# BOTTOM_1P.net
KiCad netlist of a schematic drawn in EAGLE
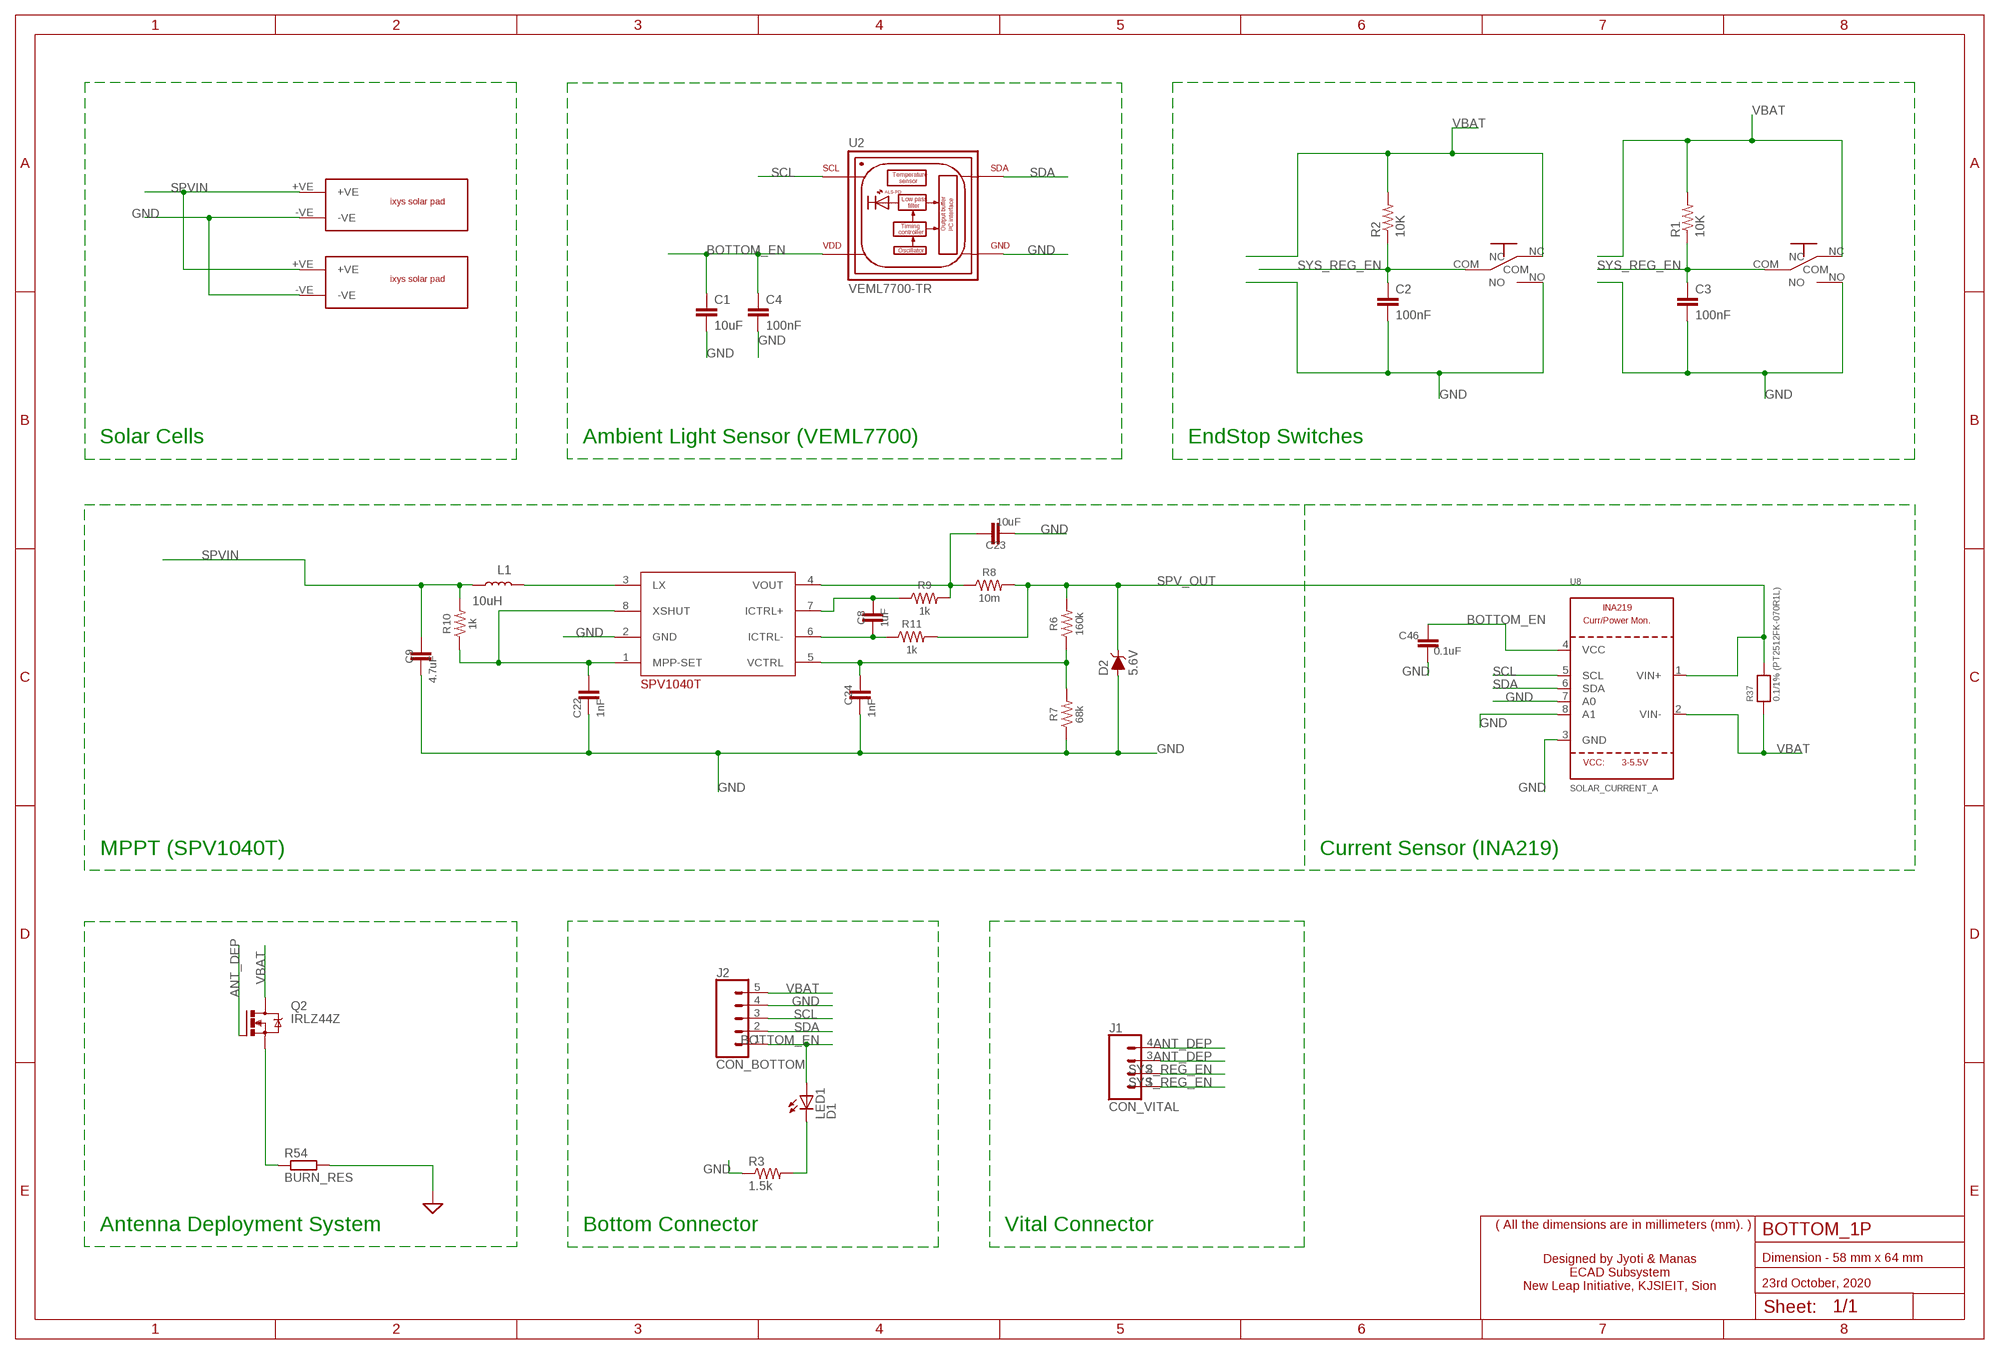
[diagram p0: schematic, sheet 1]

(export (version "E")
  (design (tool "Eeschema 10.0.6"))
  (components
    (comp (ref "C1")
      (value "10uF")
      (footprint "eagle-import:0603")
      (libsource (lib "eagle-import") (part "2.2NF/2200PF-0603-50V-10%"))
    )
    (comp (ref "C2")
      (value "100nF")
      (footprint "eagle-import:0805")
      (libsource (lib "eagle-import") (part "CAP0805"))
    )
    (comp (ref "C3")
      (value "100nF")
      (footprint "eagle-import:0805")
      (libsource (lib "eagle-import") (part "CAP0805"))
    )
    (comp (ref "C4")
      (value "100nF")
      (footprint "eagle-import:0603")
      (libsource (lib "eagle-import") (part "2.2NF/2200PF-0603-50V-10%"))
    )
    (comp (ref "C8")
      (value "1uF")
      (footprint "eagle-import:0603")
      (libsource (lib "eagle-import") (part "10UF-0603-6.3V-20%"))
    )
    (comp (ref "C9")
      (value "4.7uF")
      (footprint "eagle-import:0603")
      (libsource (lib "eagle-import") (part "10UF-0603-6.3V-20%"))
    )
    (comp (ref "C22")
      (value "1nF")
      (footprint "eagle-import:0603")
      (libsource (lib "eagle-import") (part "10UF-0603-6.3V-20%"))
    )
    (comp (ref "C23")
      (value "10uF")
      (footprint "eagle-import:0603")
      (libsource (lib "eagle-import") (part "10UF-0603-6.3V-20%"))
    )
    (comp (ref "C24")
      (value "1nF")
      (footprint "eagle-import:0603")
      (libsource (lib "eagle-import") (part "10UF-0603-6.3V-20%"))
    )
    (comp (ref "C46")
      (value "0.1uF")
      (footprint "eagle-import:0603")
      (libsource (lib "eagle-import") (part "10UF-0603-6.3V-20%"))
    )
    (comp (ref "D2")
      (value "5.6V")
      (footprint "eagle-import:SOD-323")
      (libsource (lib "eagle-import") (part "DIODE-ZENER-MMSZ5232BS"))
    )
    (comp (ref "ES1")
      (value "OMRON-D2FA")
      (footprint "eagle-import:OMRON-D2F-A")
      (libsource (lib "eagle-import") (part "OMRON-D2FA"))
    )
    (comp (ref "ES2")
      (value "OMRON-D2FA")
      (footprint "eagle-import:OMRON-D2F-A")
      (libsource (lib "eagle-import") (part "OMRON-D2FA"))
    )
    (comp (ref "J1")
      (value "CON_VITAL")
      (footprint "eagle-import:1X04_1.27MM")
      (libsource (lib "eagle-import") (part "CONN_041.27MM"))
    )
    (comp (ref "J2")
      (value "CON_BOTTOM")
      (footprint "eagle-import:1X05_1.27MM")
      (libsource (lib "eagle-import") (part "CONN_051.27MM"))
    )
    (comp (ref "L1")
      (value "10uH")
      (footprint "eagle-import:0603")
      (libsource (lib "eagle-import") (part "INDUCTOR-0603-33NH"))
    )
    (comp (ref "LED1")
      (value "D1")
      (footprint "eagle-import:CHIP-LED0603")
      (libsource (lib "eagle-import") (part "LEDCHIP-LED0603"))
    )
    (comp (ref "Q2")
      (value "IRLZ44Z")
      (footprint "eagle-import:TO220BH")
      (libsource (lib "eagle-import") (part "IRLZ44Z"))
    )
    (comp (ref "R1")
      (value "10K")
      (footprint "eagle-import:0805")
      (libsource (lib "eagle-import") (part "RESISTOR"))
    )
    (comp (ref "R2")
      (value "10K")
      (footprint "eagle-import:0805")
      (libsource (lib "eagle-import") (part "RESISTOR"))
    )
    (comp (ref "R3")
      (value "1.5k")
      (footprint "eagle-import:R0603")
      (libsource (lib "eagle-import") (part "R-US_R0603"))
    )
    (comp (ref "R6")
      (value "160k")
      (footprint "eagle-import:RES_0603")
      (fields
        (field (name "DIGIKEY_PART_NUMBER") "311-0.0GRTR-ND")
        (field (name "MANUFACTURER") "Yageo")
        (field (name "MPN") "RC0603JR-070RL")
        (field (name "CREATED_BY") "PCBLayout.com")
      )
      (libsource (lib "eagle-import") (part "RC0603JR-070RL"))
    )
    (comp (ref "R7")
      (value "68k")
      (footprint "eagle-import:RES_0603")
      (fields
        (field (name "DIGIKEY_PART_NUMBER") "311-0.0GRTR-ND")
        (field (name "MANUFACTURER") "Yageo")
        (field (name "MPN") "RC0603JR-070RL")
        (field (name "CREATED_BY") "PCBLayout.com")
      )
      (libsource (lib "eagle-import") (part "RC0603JR-070RL"))
    )
    (comp (ref "R8")
      (value "10m")
      (footprint "eagle-import:RES_0603")
      (fields
        (field (name "DIGIKEY_PART_NUMBER") "311-0.0GRTR-ND")
        (field (name "MANUFACTURER") "Yageo")
        (field (name "MPN") "RC0603JR-070RL")
        (field (name "CREATED_BY") "PCBLayout.com")
      )
      (libsource (lib "eagle-import") (part "RC0603JR-070RL"))
    )
    (comp (ref "R9")
      (value "1k")
      (footprint "eagle-import:RES_0603")
      (fields
        (field (name "DIGIKEY_PART_NUMBER") "311-0.0GRTR-ND")
        (field (name "MANUFACTURER") "Yageo")
        (field (name "MPN") "RC0603JR-070RL")
        (field (name "CREATED_BY") "PCBLayout.com")
      )
      (libsource (lib "eagle-import") (part "RC0603JR-070RL"))
    )
    (comp (ref "R10")
      (value "1k")
      (footprint "eagle-import:RES_0603")
      (fields
        (field (name "DIGIKEY_PART_NUMBER") "311-0.0GRTR-ND")
        (field (name "MANUFACTURER") "Yageo")
        (field (name "MPN") "RC0603JR-070RL")
        (field (name "CREATED_BY") "PCBLayout.com")
      )
      (libsource (lib "eagle-import") (part "RC0603JR-070RL"))
    )
    (comp (ref "R11")
      (value "1k")
      (footprint "eagle-import:RES_0603")
      (fields
        (field (name "DIGIKEY_PART_NUMBER") "311-0.0GRTR-ND")
        (field (name "MANUFACTURER") "Yageo")
        (field (name "MPN") "RC0603JR-070RL")
        (field (name "CREATED_BY") "PCBLayout.com")
      )
      (libsource (lib "eagle-import") (part "RC0603JR-070RL"))
    )
    (comp (ref "R37")
      (value "0.1/1% (PT2512FK-070R1L)")
      (footprint "eagle-import:2512")
      (libsource (lib "eagle-import") (part "RESISTOR2512"))
    )
    (comp (ref "R54")
      (value "BURN_RES")
      (footprint "eagle-import:0204V")
      (libsource (lib "eagle-import") (part "R-EU_0204/2V"))
    )
    (comp (ref "SPV_A")
      (value "SPV1040T_")
      (footprint "eagle-import:SOP65P640X120-8N")
      (libsource (lib "eagle-import") (part "SPV1040T_"))
    )
    (comp (ref "U$1")
      (value "IXYS")
      (footprint "eagle-import:IXYS")
      (libsource (lib "eagle-import") (part "IXYS"))
    )
    (comp (ref "U$2")
      (value "IXYS")
      (footprint "eagle-import:IXYS")
      (libsource (lib "eagle-import") (part "IXYS"))
    )
    (comp (ref "U2")
      (value "VEML7700-TR")
      (footprint "eagle-import:XDCR_VEML7700-TR")
      (fields (field (name "DIGI-KEY_PART_NUMBER") "VEML7700CT-ND") (field (name "MF") "Vishay"))
      (libsource (lib "eagle-import") (part "VEML7700-TR"))
    )
    (comp (ref "U8")
      (value "SOLAR_CURRENT_A")
      (footprint "eagle-import:SOT23-8")
      (libsource (lib "eagle-import") (part "INA219"))
    )
  )
  (nets
    (net (code "1") (name "/ANT_DEP") (class "Default")
      (node (ref "J1") (pin "3") (pinfunction "3_3") (pintype "passive"))
      (node (ref "J1") (pin "4") (pinfunction "4_4") (pintype "passive"))
      (node (ref "Q2") (pin "G") (pinfunction "G_G") (pintype "passive"))
    )
    (net (code "2") (name "/BOTTOM_EN") (class "Default")
      (node (ref "C1") (pin "1") (pinfunction "1_1") (pintype "passive"))
      (node (ref "C4") (pin "1") (pinfunction "1_1") (pintype "passive"))
      (node (ref "C46") (pin "1") (pinfunction "1_1") (pintype "passive"))
      (node (ref "J2") (pin "1") (pinfunction "1_1") (pintype "passive"))
      (node (ref "LED1") (pin "A") (pinfunction "A_A") (pintype "passive"))
      (node (ref "U2") (pin "2") (pinfunction "VDD_2") (pintype "power_in"))
      (node (ref "U8") (pin "4") (pinfunction "VCC_4") (pintype "bidirectional"))
    )
    (net (code "3") (name "/SCL") (class "Default")
      (node (ref "J2") (pin "3") (pinfunction "3_3") (pintype "passive"))
      (node (ref "U2") (pin "1") (pinfunction "SCL_1") (pintype "input"))
      (node (ref "U8") (pin "5") (pinfunction "SCL_5") (pintype "bidirectional"))
    )
    (net (code "4") (name "/SDA") (class "Default")
      (node (ref "J2") (pin "2") (pinfunction "2_2") (pintype "passive"))
      (node (ref "U2") (pin "4") (pinfunction "SDA_4") (pintype "bidirectional"))
      (node (ref "U8") (pin "6") (pinfunction "SDA_6") (pintype "bidirectional"))
    )
    (net (code "5") (name "/SPVIN") (class "Default")
      (node (ref "C9") (pin "1") (pinfunction "1_1") (pintype "passive"))
      (node (ref "L1") (pin "1") (pinfunction "1_1") (pintype "passive"))
      (node (ref "R10") (pin "2") (pinfunction "2_2") (pintype "passive"))
      (node (ref "U$1") (pin "+VE") (pinfunction "+VE_+VE") (pintype "bidirectional"))
      (node (ref "U$2") (pin "+VE") (pinfunction "+VE_+VE") (pintype "bidirectional"))
    )
    (net (code "6") (name "/SPV_OUT") (class "Default")
      (node (ref "D2") (pin "C") (pinfunction "C_C") (pintype "passive"))
      (node (ref "R11") (pin "2") (pinfunction "2_2") (pintype "passive"))
      (node (ref "R37") (pin "2") (pinfunction "2_2") (pintype "passive"))
      (node (ref "R6") (pin "2") (pinfunction "2_2") (pintype "passive"))
      (node (ref "R8") (pin "2") (pinfunction "2_2") (pintype "passive"))
      (node (ref "U8") (pin "1") (pinfunction "VIN+_1") (pintype "bidirectional"))
    )
    (net (code "7") (name "/SYS_REG_EN") (class "Default")
      (node (ref "C2") (pin "1") (pinfunction "1_1") (pintype "passive"))
      (node (ref "C3") (pin "1") (pinfunction "1_1") (pintype "passive"))
      (node (ref "ES1") (pin "COM") (pinfunction "COM_COM") (pintype "bidirectional"))
      (node (ref "ES2") (pin "COM") (pinfunction "COM_COM") (pintype "bidirectional"))
      (node (ref "J1") (pin "1") (pinfunction "1_1") (pintype "passive"))
      (node (ref "J1") (pin "2") (pinfunction "2_2") (pintype "passive"))
      (node (ref "R1") (pin "1") (pinfunction "1_1") (pintype "passive"))
      (node (ref "R2") (pin "1") (pinfunction "1_1") (pintype "passive"))
    )
    (net (code "8") (name "/VBAT") (class "Default")
      (node (ref "ES1") (pin "NC") (pinfunction "NC_NC") (pintype "bidirectional"))
      (node (ref "ES2") (pin "NC") (pinfunction "NC_NC") (pintype "bidirectional"))
      (node (ref "J2") (pin "5") (pinfunction "5_5") (pintype "passive"))
      (node (ref "Q2") (pin "D") (pinfunction "D_D") (pintype "passive"))
      (node (ref "R1") (pin "2") (pinfunction "2_2") (pintype "passive"))
      (node (ref "R2") (pin "2") (pinfunction "2_2") (pintype "passive"))
      (node (ref "R37") (pin "1") (pinfunction "1_1") (pintype "passive"))
      (node (ref "U8") (pin "2") (pinfunction "VIN-_2") (pintype "bidirectional"))
    )
    (net (code "9") (name "Net-(LED1-PadC)") (class "Default")
      (node (ref "LED1") (pin "C") (pinfunction "C_C") (pintype "passive"))
      (node (ref "R3") (pin "2") (pinfunction "2_2") (pintype "passive"))
    )
    (net (code "10") (name "Net-(Q2-PadS)") (class "Default")
      (node (ref "Q2") (pin "S") (pinfunction "S_S") (pintype "passive"))
      (node (ref "R54") (pin "1") (pinfunction "1_1") (pintype "passive"))
    )
    (net (code "11") (name "Net-(SPV_A-ICTRL+)") (class "Default")
      (node (ref "C8") (pin "1") (pinfunction "1_1") (pintype "passive"))
      (node (ref "R9") (pin "1") (pinfunction "1_1") (pintype "passive"))
      (node (ref "SPV_A") (pin "7") (pinfunction "ICTRL+_7") (pintype "bidirectional"))
    )
    (net (code "12") (name "Net-(SPV_A-ICTRL-)") (class "Default")
      (node (ref "C8") (pin "2") (pinfunction "2_2") (pintype "passive"))
      (node (ref "R11") (pin "1") (pinfunction "1_1") (pintype "passive"))
      (node (ref "SPV_A") (pin "6") (pinfunction "ICTRL-_6") (pintype "bidirectional"))
    )
    (net (code "13") (name "Net-(SPV_A-LX)") (class "Default")
      (node (ref "L1") (pin "2") (pinfunction "2_2") (pintype "passive"))
      (node (ref "SPV_A") (pin "3") (pinfunction "LX_3") (pintype "bidirectional"))
    )
    (net (code "14") (name "Net-(SPV_A-MPP-SET)") (class "Default")
      (node (ref "C22") (pin "1") (pinfunction "1_1") (pintype "passive"))
      (node (ref "R10") (pin "1") (pinfunction "1_1") (pintype "passive"))
      (node (ref "SPV_A") (pin "1") (pinfunction "MPP-SET_1") (pintype "bidirectional"))
      (node (ref "SPV_A") (pin "8") (pinfunction "XSHUT_8") (pintype "bidirectional"))
    )
    (net (code "15") (name "Net-(SPV_A-VCTRL)") (class "Default")
      (node (ref "C24") (pin "1") (pinfunction "1_1") (pintype "passive"))
      (node (ref "R6") (pin "1") (pinfunction "1_1") (pintype "passive"))
      (node (ref "R7") (pin "2") (pinfunction "2_2") (pintype "passive"))
      (node (ref "SPV_A") (pin "5") (pinfunction "VCTRL_5") (pintype "bidirectional"))
    )
    (net (code "16") (name "Net-(SPV_A-VOUT)") (class "Default")
      (node (ref "C23") (pin "1") (pinfunction "1_1") (pintype "passive"))
      (node (ref "R8") (pin "1") (pinfunction "1_1") (pintype "passive"))
      (node (ref "R9") (pin "2") (pinfunction "2_2") (pintype "passive"))
      (node (ref "SPV_A") (pin "4") (pinfunction "VOUT_4") (pintype "bidirectional"))
    )
    (net (code "17") (name "SUP") (class "Default")
      (node (ref "C1") (pin "2") (pinfunction "2_2") (pintype "passive"))
      (node (ref "C2") (pin "2") (pinfunction "2_2") (pintype "passive"))
      (node (ref "C22") (pin "2") (pinfunction "2_2") (pintype "passive"))
      (node (ref "C23") (pin "2") (pinfunction "2_2") (pintype "passive"))
      (node (ref "C24") (pin "2") (pinfunction "2_2") (pintype "passive"))
      (node (ref "C3") (pin "2") (pinfunction "2_2") (pintype "passive"))
      (node (ref "C4") (pin "2") (pinfunction "2_2") (pintype "passive"))
      (node (ref "C46") (pin "2") (pinfunction "2_2") (pintype "passive"))
      (node (ref "C9") (pin "2") (pinfunction "2_2") (pintype "passive"))
      (node (ref "D2") (pin "A") (pinfunction "A_A") (pintype "passive"))
      (node (ref "ES1") (pin "NO") (pinfunction "NO_NO") (pintype "bidirectional"))
      (node (ref "ES2") (pin "NO") (pinfunction "NO_NO") (pintype "bidirectional"))
      (node (ref "J2") (pin "4") (pinfunction "4_4") (pintype "passive"))
      (node (ref "R3") (pin "1") (pinfunction "1_1") (pintype "passive"))
      (node (ref "R54") (pin "2") (pinfunction "2_2") (pintype "passive"))
      (node (ref "R7") (pin "1") (pinfunction "1_1") (pintype "passive"))
      (node (ref "SPV_A") (pin "2") (pinfunction "GND_2") (pintype "bidirectional"))
      (node (ref "U$1") (pin "-VE") (pinfunction "-VE_-VE") (pintype "bidirectional"))
      (node (ref "U$2") (pin "-VE") (pinfunction "-VE_-VE") (pintype "bidirectional"))
      (node (ref "U2") (pin "3") (pinfunction "GND_3") (pintype "power_in"))
      (node (ref "U8") (pin "3") (pinfunction "GND_3") (pintype "bidirectional"))
      (node (ref "U8") (pin "7") (pinfunction "A0_7") (pintype "bidirectional"))
      (node (ref "U8") (pin "8") (pinfunction "A1_8") (pintype "bidirectional"))
    )
  )
)
